# CAN.net
KiCad netlist of a schematic drawn in Altium Designer
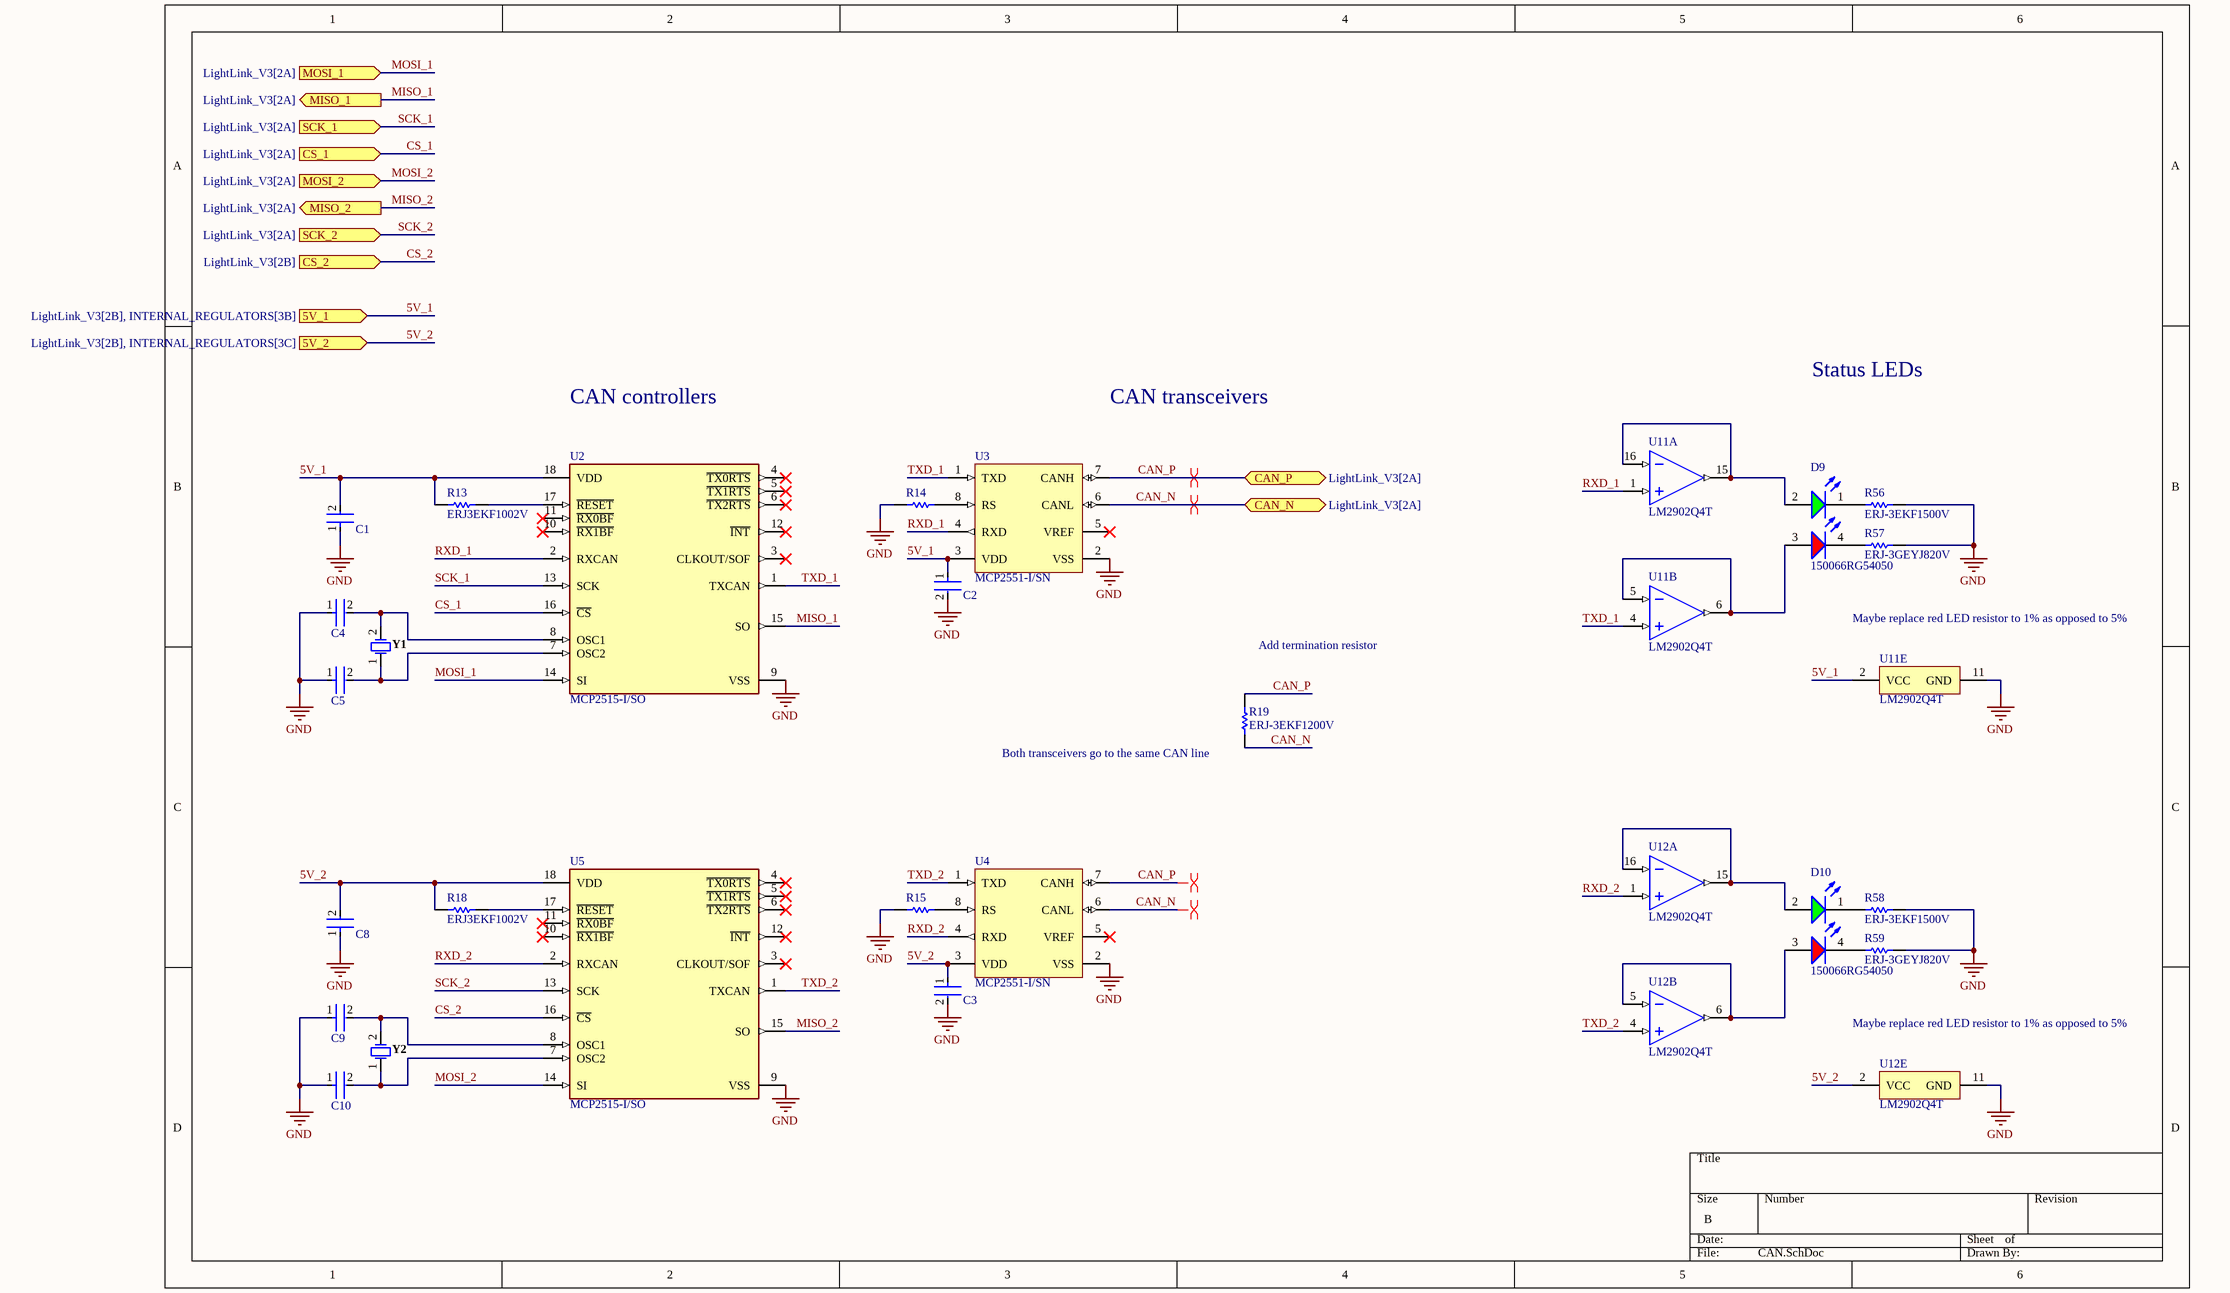
[diagram p0: CAN.SchDoc]

(export (version "E")
  (design (tool "Eeschema 10.0.6"))
  (components
    (comp (ref "C1")
      (value "GRM188R60J106ME47D")
      (footprint "FP-GRM188-0_1-e0_2_0_55-IPC_A")
      (description "Chip Multilayer Ceramic Capacitors for General Purpose, 0603, 10uF, X5R, 15%, 20%, 6.3V")
      (fields (field (name "VOLTAGE") "6.3V") (field (name "TOLERANCE") "20%"))
      (libsource (lib "Altium Content Vault") (part "02cd4be3c70576c341d710602a673aa"))
    )
    (comp (ref "C2")
      (value "C0402C104K8PACTU")
      (footprint "FP-C0402-BB-MFG")
      (description "CAP CER 0.1UF 10V X5R 0402")
      (fields (field (name "MANUFACTURER") "Kemet") (field (name "TOLERANCE") "0.1"))
      (libsource (lib "Altium Content Vault") (part "b4654b650e69147ec39a6b967a45e02"))
    )
    (comp (ref "C3")
      (value "C0402C104K8PACTU")
      (footprint "FP-C0402-BB-MFG")
      (description "CAP CER 0.1UF 10V X5R 0402")
      (fields (field (name "MANUFACTURER") "Kemet") (field (name "TOLERANCE") "0.1"))
      (libsource (lib "Altium Content Vault") (part "b4654b650e69147ec39a6b967a45e02"))
    )
    (comp (ref "C4")
      (value "GRM188R60J106ME47D")
      (footprint "FP-GRM188-0_1-e0_2_0_55-IPC_A")
      (description "Chip Multilayer Ceramic Capacitors for General Purpose, 0603, 10uF, X5R, 15%, 20%, 6.3V")
      (fields (field (name "VOLTAGE") "6.3V") (field (name "TOLERANCE") "20%"))
      (libsource (lib "Altium Content Vault") (part "02cd4be3c70576c341d710602a673aa"))
    )
    (comp (ref "C5")
      (value "GRM188R60J106ME47D")
      (footprint "FP-GRM188-0_1-e0_2_0_55-IPC_A")
      (description "Chip Multilayer Ceramic Capacitors for General Purpose, 0603, 10uF, X5R, 15%, 20%, 6.3V")
      (fields (field (name "VOLTAGE") "6.3V") (field (name "TOLERANCE") "20%"))
      (libsource (lib "Altium Content Vault") (part "02cd4be3c70576c341d710602a673aa"))
    )
    (comp (ref "C8")
      (value "GRM188R60J106ME47D")
      (footprint "FP-GRM188-0_1-e0_2_0_55-IPC_A")
      (description "Chip Multilayer Ceramic Capacitors for General Purpose, 0603, 10uF, X5R, 15%, 20%, 6.3V")
      (fields (field (name "VOLTAGE") "6.3V") (field (name "TOLERANCE") "20%"))
      (libsource (lib "Altium Content Vault") (part "02cd4be3c70576c341d710602a673aa"))
    )
    (comp (ref "C9")
      (value "GRM188R60J106ME47D")
      (footprint "FP-GRM188-0_1-e0_2_0_55-IPC_A")
      (description "Chip Multilayer Ceramic Capacitors for General Purpose, 0603, 10uF, X5R, 15%, 20%, 6.3V")
      (fields (field (name "VOLTAGE") "6.3V") (field (name "TOLERANCE") "20%"))
      (libsource (lib "Altium Content Vault") (part "02cd4be3c70576c341d710602a673aa"))
    )
    (comp (ref "C10")
      (value "GRM188R60J106ME47D")
      (footprint "FP-GRM188-0_1-e0_2_0_55-IPC_A")
      (description "Chip Multilayer Ceramic Capacitors for General Purpose, 0603, 10uF, X5R, 15%, 20%, 6.3V")
      (fields (field (name "VOLTAGE") "6.3V") (field (name "TOLERANCE") "20%"))
      (libsource (lib "Altium Content Vault") (part "02cd4be3c70576c341d710602a673aa"))
    )
    (comp (ref "D9")
      (value "150066RG54050")
      (footprint "WL-SBCD_0606")
      (description "Led, Red/Grn, 180Mcd/230Mcd, 624Nm/525Nm Rohs Compliant: Yes")
      (libsource (lib "uORocketry Hardware") (part "WL-SBCD_0606_Red & Green"))
    )
    (comp (ref "D10")
      (value "150066RG54050")
      (footprint "WL-SBCD_0606")
      (description "Led, Red/Grn, 180Mcd/230Mcd, 624Nm/525Nm Rohs Compliant: Yes")
      (libsource (lib "uORocketry Hardware") (part "WL-SBCD_0606_Red & Green"))
    )
    (comp (ref "R13")
      (value "ERJ3EKF1002V")
      (footprint "RESC1609X55X30LL15T15")
      (description "Chip Resistor, 10 KOhm, +/- 1%, 0.1 W, -55 to 155 degC, 0603 (1608 Metric), RoHS, Tape and Reel")
      (fields (field (name "TOLERANCE") "1%") (field (name "MANUFACTURER") "Panasonic"))
      (libsource (lib "Altium Content Vault") (part "RES-2"))
    )
    (comp (ref "R14")
      (value "ERJ3EKF1002V")
      (footprint "RESC1609X55X30LL15T15")
      (description "Chip Resistor, 10 KOhm, +/- 1%, 0.1 W, -55 to 155 degC, 0603 (1608 Metric), RoHS, Tape and Reel")
      (fields (field (name "TOLERANCE") "1%") (field (name "MANUFACTURER") "Panasonic"))
      (libsource (lib "Altium Content Vault") (part "RES-2"))
    )
    (comp (ref "R15")
      (value "ERJ3EKF1002V")
      (footprint "RESC1609X55X30LL15T15")
      (description "Chip Resistor, 10 KOhm, +/- 1%, 0.1 W, -55 to 155 degC, 0603 (1608 Metric), RoHS, Tape and Reel")
      (fields (field (name "TOLERANCE") "1%") (field (name "MANUFACTURER") "Panasonic"))
      (libsource (lib "Altium Content Vault") (part "RES-2"))
    )
    (comp (ref "R18")
      (value "ERJ3EKF1002V")
      (footprint "RESC1609X55X30LL15T15")
      (description "Chip Resistor, 10 KOhm, +/- 1%, 0.1 W, -55 to 155 degC, 0603 (1608 Metric), RoHS, Tape and Reel")
      (fields (field (name "TOLERANCE") "1%") (field (name "MANUFACTURER") "Panasonic"))
      (libsource (lib "Altium Content Vault") (part "RES-2"))
    )
    (comp (ref "R19")
      (value "ERJ-3EKF1200V")
      (footprint "RESC1609X55X30ML15T15")
      (description "Chip Resistor, 120 Ohm, +/- 1%, 0.1 W, -55 to 155 degC, 0603 (1608 Metric), RoHS, Tape and Reel")
      (fields (field (name "TOLERANCE") "1%") (field (name "MANUFACTURER") "Panasonic"))
      (libsource (lib "Altium Content Vault") (part "RES-2"))
    )
    (comp (ref "R56")
      (value "ERJ-3EKF1500V")
      (footprint "RESC1608X55X30NL15T15")
      (fields (field (name "MANUFACTURER") "Panasonic"))
      (libsource (lib "Altium Content Vault") (part "RES"))
    )
    (comp (ref "R57")
      (value "ERJ-3GEYJ820V")
      (footprint "RESC1608X55X30NL15T15")
      (fields (field (name "MANUFACTURER") "Panasonic"))
      (libsource (lib "Altium Content Vault") (part "RES"))
    )
    (comp (ref "R58")
      (value "ERJ-3EKF1500V")
      (footprint "RESC1608X55X30NL15T15")
      (fields (field (name "MANUFACTURER") "Panasonic"))
      (libsource (lib "Altium Content Vault") (part "RES"))
    )
    (comp (ref "R59")
      (value "ERJ-3GEYJ820V")
      (footprint "RESC1608X55X30NL15T15")
      (fields (field (name "MANUFACTURER") "Panasonic"))
      (libsource (lib "Altium Content Vault") (part "RES"))
    )
    (comp (ref "U2")
      (value "MCP2515-I/SO")
      (footprint "FP-C04-051-MFG")
      (description "IC CAN CONTROLLER W/SPI 18SOIC")
      (fields
        (field (name "MANUFACTURER") "Microchip")
        (field (name "OCTOPART") "https://octopart.com/mcp2515-i%2Fso-microchip-430187")
      )
      (libsource (lib "Altium Content Vault") (part "1c78ea6ff576bac94664e2637e1b479"))
    )
    (comp (ref "U3")
      (value "MCP2551-I/SN")
      (footprint "MCHP-SN8_V")
      (fields (field (name "MANUFACTURER") "Microchip"))
      (libsource (lib "Altium Content Vault") (part "MCHP-MCP2551-SN8"))
    )
    (comp (ref "U4")
      (value "MCP2551-I/SN")
      (footprint "MCHP-SN8_V")
      (fields (field (name "MANUFACTURER") "Microchip"))
      (libsource (lib "Altium Content Vault") (part "MCHP-MCP2551-SN8"))
    )
    (comp (ref "U5")
      (value "MCP2515-I/SO")
      (footprint "FP-C04-051-MFG")
      (description "IC CAN CONTROLLER W/SPI 18SOIC")
      (fields
        (field (name "MANUFACTURER") "Microchip")
        (field (name "OCTOPART") "https://octopart.com/mcp2515-i%2Fso-microchip-430187")
      )
      (libsource (lib "Altium Content Vault") (part "1c78ea6ff576bac94664e2637e1b479"))
    )
    (comp (ref "U11")
      (value "LM2902Q4T")
      (footprint "LM2902Q4T-Footprint-1")
      (description "LM2902 Series 30 V 1.3 MHz Low-Power Quad Operational Amplifier - QFN-16 (3x3)")
      (libsource (lib "uORocketry Hardware") (part "LM2902Q4T"))
    )
    (comp (ref "U12")
      (value "LM2902Q4T")
      (footprint "LM2902Q4T-Footprint-1")
      (description "LM2902 Series 30 V 1.3 MHz Low-Power Quad Operational Amplifier - QFN-16 (3x3)")
      (libsource (lib "uORocketry Hardware") (part "LM2902Q4T"))
    )
    (comp (ref "Y1")
      (value "FOXSLF/160-20")
      (footprint "FOX-FOXSLF160-20")
      (description "Resistance Weld Thru-Hole Crystal, 16 MHz, -20 to 70 degC, 2-Pin THD, RoHS, Bulk")
      (fields (field (name "TOLERANCE") "1%"))
      (libsource (lib "Altium Content Vault") (part "XTAL-1-2-2"))
    )
    (comp (ref "Y2")
      (value "FOXSLF/160-20")
      (footprint "FOX-FOXSLF160-20")
      (description "Resistance Weld Thru-Hole Crystal, 16 MHz, -20 to 70 degC, 2-Pin THD, RoHS, Bulk")
      (fields (field (name "TOLERANCE") "1%"))
      (libsource (lib "Altium Content Vault") (part "XTAL-1-2-2"))
    )
  )
  (nets
    (net (code "1") (name "/5V_1") (class "Default")
      (node (ref "C1") (pin "2") (pinfunction "2_2") (pintype "passive"))
      (node (ref "C2") (pin "1") (pinfunction "1_1") (pintype "passive"))
      (node (ref "R13") (pin "1") (pinfunction "1_1") (pintype "passive"))
      (node (ref "U11") (pin "2") (pinfunction "VCC_2") (pintype "power_in"))
      (node (ref "U2") (pin "18") (pinfunction "VDD_18") (pintype "power_in"))
      (node (ref "U3") (pin "3") (pinfunction "VDD_3") (pintype "power_in"))
    )
    (net (code "2") (name "/5V_2") (class "Default")
      (node (ref "C3") (pin "1") (pinfunction "1_1") (pintype "passive"))
      (node (ref "C8") (pin "2") (pinfunction "2_2") (pintype "passive"))
      (node (ref "R18") (pin "1") (pinfunction "1_1") (pintype "passive"))
      (node (ref "U12") (pin "2") (pinfunction "VCC_2") (pintype "power_in"))
      (node (ref "U4") (pin "3") (pinfunction "VDD_3") (pintype "power_in"))
      (node (ref "U5") (pin "18") (pinfunction "VDD_18") (pintype "power_in"))
    )
    (net (code "3") (name "/CAN_N") (class "Default")
      (node (ref "R19") (pin "1") (pinfunction "1_1") (pintype "passive"))
      (node (ref "U3") (pin "6") (pinfunction "CANL_6") (pintype "bidirectional"))
      (node (ref "U4") (pin "6") (pinfunction "CANL_6") (pintype "bidirectional"))
    )
    (net (code "4") (name "/CAN_P") (class "Default")
      (node (ref "R19") (pin "2") (pinfunction "2_2") (pintype "passive"))
      (node (ref "U3") (pin "7") (pinfunction "CANH_7") (pintype "bidirectional"))
      (node (ref "U4") (pin "7") (pinfunction "CANH_7") (pintype "bidirectional"))
    )
    (net (code "5") (name "/CS_1") (class "Default")
      (node (ref "U2") (pin "16") (pinfunction "~{CS}_16") (pintype "input"))
    )
    (net (code "6") (name "/CS_2") (class "Default")
      (node (ref "U5") (pin "16") (pinfunction "~{CS}_16") (pintype "input"))
    )
    (net (code "7") (name "/MISO_1") (class "Default")
      (node (ref "U2") (pin "15") (pinfunction "SO_15") (pintype "output"))
    )
    (net (code "8") (name "/MISO_2") (class "Default")
      (node (ref "U5") (pin "15") (pinfunction "SO_15") (pintype "output"))
    )
    (net (code "9") (name "/MOSI_1") (class "Default")
      (node (ref "U2") (pin "14") (pinfunction "SI_14") (pintype "input"))
    )
    (net (code "10") (name "/MOSI_2") (class "Default")
      (node (ref "U5") (pin "14") (pinfunction "SI_14") (pintype "input"))
    )
    (net (code "11") (name "/RXD_1") (class "Default")
      (node (ref "U11") (pin "1") (pinfunction "1IN+_1") (pintype "input"))
      (node (ref "U2") (pin "2") (pinfunction "RXCAN_2") (pintype "input"))
      (node (ref "U3") (pin "4") (pinfunction "RXD_4") (pintype "output"))
    )
    (net (code "12") (name "/RXD_2") (class "Default")
      (node (ref "U12") (pin "1") (pinfunction "1IN+_1") (pintype "input"))
      (node (ref "U4") (pin "4") (pinfunction "RXD_4") (pintype "output"))
      (node (ref "U5") (pin "2") (pinfunction "RXCAN_2") (pintype "input"))
    )
    (net (code "13") (name "/SCK_1") (class "Default")
      (node (ref "U2") (pin "13") (pinfunction "SCK_13") (pintype "input"))
    )
    (net (code "14") (name "/SCK_2") (class "Default")
      (node (ref "U5") (pin "13") (pinfunction "SCK_13") (pintype "input"))
    )
    (net (code "15") (name "/TXD_1") (class "Default")
      (node (ref "U11") (pin "4") (pinfunction "2IN+_4") (pintype "input"))
      (node (ref "U2") (pin "1") (pinfunction "TXCAN_1") (pintype "output"))
      (node (ref "U3") (pin "1") (pinfunction "TXD_1") (pintype "input"))
    )
    (net (code "16") (name "/TXD_2") (class "Default")
      (node (ref "U12") (pin "4") (pinfunction "2IN+_4") (pintype "input"))
      (node (ref "U4") (pin "1") (pinfunction "TXD_1") (pintype "input"))
      (node (ref "U5") (pin "1") (pinfunction "TXCAN_1") (pintype "output"))
    )
    (net (code "17") (name "GND") (class "Default")
      (node (ref "C1") (pin "1") (pinfunction "1_1") (pintype "passive"))
      (node (ref "C10") (pin "1") (pinfunction "1_1") (pintype "passive"))
      (node (ref "C2") (pin "2") (pinfunction "2_2") (pintype "passive"))
      (node (ref "C3") (pin "2") (pinfunction "2_2") (pintype "passive"))
      (node (ref "C4") (pin "1") (pinfunction "1_1") (pintype "passive"))
      (node (ref "C5") (pin "1") (pinfunction "1_1") (pintype "passive"))
      (node (ref "C8") (pin "1") (pinfunction "1_1") (pintype "passive"))
      (node (ref "C9") (pin "1") (pinfunction "1_1") (pintype "passive"))
      (node (ref "R14") (pin "1") (pinfunction "1_1") (pintype "passive"))
      (node (ref "R15") (pin "1") (pinfunction "1_1") (pintype "passive"))
      (node (ref "R56") (pin "2") (pinfunction "2_2") (pintype "passive"))
      (node (ref "R57") (pin "2") (pinfunction "2_2") (pintype "passive"))
      (node (ref "R58") (pin "2") (pinfunction "2_2") (pintype "passive"))
      (node (ref "R59") (pin "2") (pinfunction "2_2") (pintype "passive"))
      (node (ref "U11") (pin "11") (pinfunction "GND_11") (pintype "power_in"))
      (node (ref "U12") (pin "11") (pinfunction "GND_11") (pintype "power_in"))
      (node (ref "U2") (pin "9") (pinfunction "VSS_9") (pintype "power_in"))
      (node (ref "U3") (pin "2") (pinfunction "VSS_2") (pintype "power_in"))
      (node (ref "U4") (pin "2") (pinfunction "VSS_2") (pintype "power_in"))
      (node (ref "U5") (pin "9") (pinfunction "VSS_9") (pintype "power_in"))
    )
    (net (code "18") (name "Net-(D9-K-Pad1)") (class "Default")
      (node (ref "D9") (pin "1") (pinfunction "K_1") (pintype "passive"))
      (node (ref "R56") (pin "1") (pinfunction "1_1") (pintype "passive"))
    )
    (net (code "19") (name "Net-(D9-K-Pad4)") (class "Default")
      (node (ref "D9") (pin "4") (pinfunction "K_4") (pintype "passive"))
      (node (ref "R57") (pin "1") (pinfunction "1_1") (pintype "passive"))
    )
    (net (code "20") (name "Net-(D10-K-Pad1)") (class "Default")
      (node (ref "D10") (pin "1") (pinfunction "K_1") (pintype "passive"))
      (node (ref "R58") (pin "1") (pinfunction "1_1") (pintype "passive"))
    )
    (net (code "21") (name "Net-(D10-K-Pad4)") (class "Default")
      (node (ref "D10") (pin "4") (pinfunction "K_4") (pintype "passive"))
      (node (ref "R59") (pin "1") (pinfunction "1_1") (pintype "passive"))
    )
    (net (code "22") (name "Net-(U2-OSC1)") (class "Default")
      (node (ref "C4") (pin "2") (pinfunction "2_2") (pintype "passive"))
      (node (ref "U2") (pin "8") (pinfunction "OSC1_8") (pintype "input"))
      (node (ref "Y1") (pin "2") (pinfunction "2_2") (pintype "passive"))
    )
    (net (code "23") (name "Net-(U2-OSC2)") (class "Default")
      (node (ref "C5") (pin "2") (pinfunction "2_2") (pintype "passive"))
      (node (ref "U2") (pin "7") (pinfunction "OSC2_7") (pintype "input"))
      (node (ref "Y1") (pin "1") (pinfunction "1_1") (pintype "passive"))
    )
    (net (code "24") (name "Net-(U2-~{RESET})") (class "Default")
      (node (ref "R13") (pin "2") (pinfunction "2_2") (pintype "passive"))
      (node (ref "U2") (pin "17") (pinfunction "~{RESET}_17") (pintype "input"))
    )
    (net (code "25") (name "Net-(U3-RS)") (class "Default")
      (node (ref "R14") (pin "2") (pinfunction "2_2") (pintype "passive"))
      (node (ref "U3") (pin "8") (pinfunction "RS_8") (pintype "input"))
    )
    (net (code "26") (name "Net-(U4-RS)") (class "Default")
      (node (ref "R15") (pin "2") (pinfunction "2_2") (pintype "passive"))
      (node (ref "U4") (pin "8") (pinfunction "RS_8") (pintype "input"))
    )
    (net (code "27") (name "Net-(U5-OSC1)") (class "Default")
      (node (ref "C9") (pin "2") (pinfunction "2_2") (pintype "passive"))
      (node (ref "U5") (pin "8") (pinfunction "OSC1_8") (pintype "input"))
      (node (ref "Y2") (pin "2") (pinfunction "2_2") (pintype "passive"))
    )
    (net (code "28") (name "Net-(U5-OSC2)") (class "Default")
      (node (ref "C10") (pin "2") (pinfunction "2_2") (pintype "passive"))
      (node (ref "U5") (pin "7") (pinfunction "OSC2_7") (pintype "input"))
      (node (ref "Y2") (pin "1") (pinfunction "1_1") (pintype "passive"))
    )
    (net (code "29") (name "Net-(U5-~{RESET})") (class "Default")
      (node (ref "R18") (pin "2") (pinfunction "2_2") (pintype "passive"))
      (node (ref "U5") (pin "17") (pinfunction "~{RESET}_17") (pintype "input"))
    )
    (net (code "30") (name "Net-(U11A-1IN-)") (class "Default")
      (node (ref "D9") (pin "2") (pinfunction "A_2") (pintype "passive"))
      (node (ref "U11") (pin "15") (pinfunction "1OUT_15") (pintype "output"))
      (node (ref "U11") (pin "16") (pinfunction "1IN-_16") (pintype "input"))
    )
    (net (code "31") (name "Net-(U11B-2IN-)") (class "Default")
      (node (ref "D9") (pin "3") (pinfunction "A_3") (pintype "passive"))
      (node (ref "U11") (pin "5") (pinfunction "2IN-_5") (pintype "input"))
      (node (ref "U11") (pin "6") (pinfunction "2OUT_6") (pintype "output"))
    )
    (net (code "32") (name "Net-(U12A-1IN-)") (class "Default")
      (node (ref "D10") (pin "2") (pinfunction "A_2") (pintype "passive"))
      (node (ref "U12") (pin "15") (pinfunction "1OUT_15") (pintype "output"))
      (node (ref "U12") (pin "16") (pinfunction "1IN-_16") (pintype "input"))
    )
    (net (code "33") (name "Net-(U12B-2IN-)") (class "Default")
      (node (ref "D10") (pin "3") (pinfunction "A_3") (pintype "passive"))
      (node (ref "U12") (pin "5") (pinfunction "2IN-_5") (pintype "input"))
      (node (ref "U12") (pin "6") (pinfunction "2OUT_6") (pintype "output"))
    )
    (net (code "34") (name "unconnected-(U2-CLKOUT{slash}SOF-Pad3)") (class "Default")
      (node (ref "U2") (pin "3") (pinfunction "CLKOUT/SOF_3") (pintype "output+no_connect"))
    )
    (net (code "35") (name "unconnected-(U2-~{INT}-Pad12)") (class "Default")
      (node (ref "U2") (pin "12") (pinfunction "~{INT}_12") (pintype "output+no_connect"))
    )
    (net (code "36") (name "unconnected-(U2-~{RX0BF}-Pad11)") (class "Default")
      (node (ref "U2") (pin "11") (pinfunction "~{RX0BF}_11") (pintype "input+no_connect"))
    )
    (net (code "37") (name "unconnected-(U2-~{RX1BF}-Pad10)") (class "Default")
      (node (ref "U2") (pin "10") (pinfunction "~{RX1BF}_10") (pintype "input+no_connect"))
    )
    (net (code "38") (name "unconnected-(U2-~{TX0RTS}-Pad4)") (class "Default")
      (node (ref "U2") (pin "4") (pinfunction "~{TX0RTS}_4") (pintype "output+no_connect"))
    )
    (net (code "39") (name "unconnected-(U2-~{TX1RTS}-Pad5)") (class "Default")
      (node (ref "U2") (pin "5") (pinfunction "~{TX1RTS}_5") (pintype "output+no_connect"))
    )
    (net (code "40") (name "unconnected-(U2-~{TX2RTS}-Pad6)") (class "Default")
      (node (ref "U2") (pin "6") (pinfunction "~{TX2RTS}_6") (pintype "output+no_connect"))
    )
    (net (code "41") (name "unconnected-(U3-VREF-Pad5)") (class "Default")
      (node (ref "U3") (pin "5") (pinfunction "VREF_5") (pintype "power_in+no_connect"))
    )
    (net (code "42") (name "unconnected-(U4-VREF-Pad5)") (class "Default")
      (node (ref "U4") (pin "5") (pinfunction "VREF_5") (pintype "power_in+no_connect"))
    )
    (net (code "43") (name "unconnected-(U5-CLKOUT{slash}SOF-Pad3)") (class "Default")
      (node (ref "U5") (pin "3") (pinfunction "CLKOUT/SOF_3") (pintype "output+no_connect"))
    )
    (net (code "44") (name "unconnected-(U5-~{INT}-Pad12)") (class "Default")
      (node (ref "U5") (pin "12") (pinfunction "~{INT}_12") (pintype "output+no_connect"))
    )
    (net (code "45") (name "unconnected-(U5-~{RX0BF}-Pad11)") (class "Default")
      (node (ref "U5") (pin "11") (pinfunction "~{RX0BF}_11") (pintype "input+no_connect"))
    )
    (net (code "46") (name "unconnected-(U5-~{RX1BF}-Pad10)") (class "Default")
      (node (ref "U5") (pin "10") (pinfunction "~{RX1BF}_10") (pintype "input+no_connect"))
    )
    (net (code "47") (name "unconnected-(U5-~{TX0RTS}-Pad4)") (class "Default")
      (node (ref "U5") (pin "4") (pinfunction "~{TX0RTS}_4") (pintype "output+no_connect"))
    )
    (net (code "48") (name "unconnected-(U5-~{TX1RTS}-Pad5)") (class "Default")
      (node (ref "U5") (pin "5") (pinfunction "~{TX1RTS}_5") (pintype "output+no_connect"))
    )
    (net (code "49") (name "unconnected-(U5-~{TX2RTS}-Pad6)") (class "Default")
      (node (ref "U5") (pin "6") (pinfunction "~{TX2RTS}_6") (pintype "output+no_connect"))
    )
  )
)
